# Stromversorgung-3.net
KiCad netlist of a schematic drawn in EAGLE
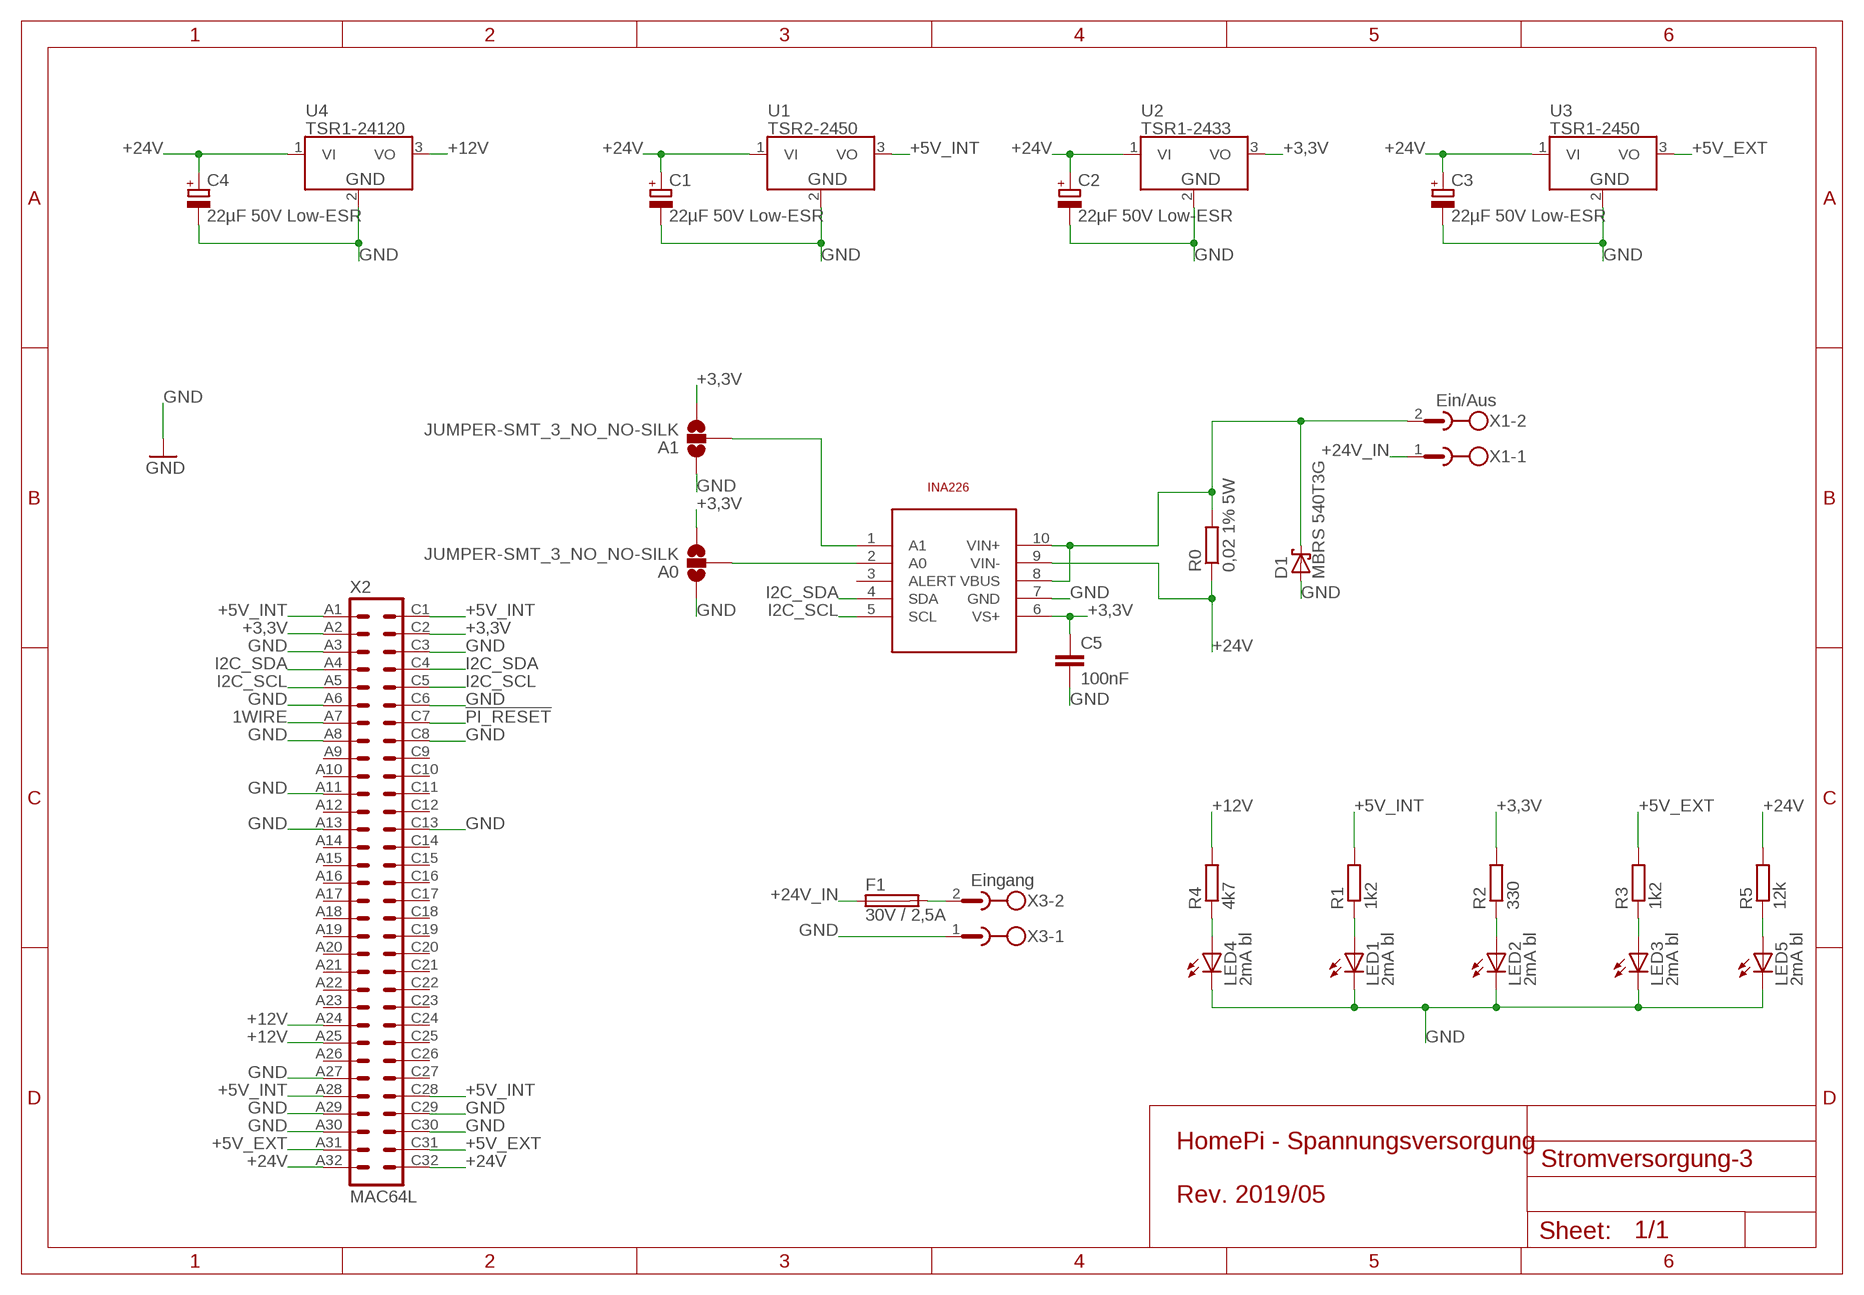
[diagram p0: schematic, sheet 1]

(export (version "E")
  (design (tool "Eeschema 10.0.6"))
  (components
    (comp (ref "A0")
      (value "JUMPER-SMT_3_NO_NO-SILK")
      (footprint "eagle-import:SMT-JUMPER_3_NO_NO-SILK")
      (libsource (lib "eagle-import") (part "JUMPER-SMT_3_NO_NO-SILK"))
    )
    (comp (ref "A1")
      (value "JUMPER-SMT_3_NO_NO-SILK")
      (footprint "eagle-import:SMT-JUMPER_3_NO_NO-SILK")
      (libsource (lib "eagle-import") (part "JUMPER-SMT_3_NO_NO-SILK"))
    )
    (comp (ref "C1")
      (value "22µF 50V Low-ESR")
      (footprint "eagle-import:E2-5")
      (libsource (lib "eagle-import") (part "CPOL-EUE2-5"))
    )
    (comp (ref "C2")
      (value "22µF 50V Low-ESR")
      (footprint "eagle-import:E2-5")
      (libsource (lib "eagle-import") (part "CPOL-EUE2-5"))
    )
    (comp (ref "C3")
      (value "22µF 50V Low-ESR")
      (footprint "eagle-import:E2-5")
      (libsource (lib "eagle-import") (part "CPOL-EUE2-5"))
    )
    (comp (ref "C4")
      (value "22µF 50V Low-ESR")
      (footprint "eagle-import:E2-5")
      (libsource (lib "eagle-import") (part "CPOL-EUE2-5"))
    )
    (comp (ref "C5")
      (value "100nF")
      (footprint "eagle-import:C1206")
      (libsource (lib "eagle-import") (part "C-EUC1206"))
    )
    (comp (ref "D1")
      (value "MBRS 540T3G")
      (footprint "eagle-import:SMC")
      (libsource (lib "eagle-import") (part "SCHOTTKY-DIODESMC"))
    )
    (comp (ref "F1")
      (value "30V / 2,5A")
      (footprint "eagle-import:LITTLEFUSE")
      (libsource (lib "eagle-import") (part "LITTLEFUSE"))
    )
    (comp (ref "IC1")
      (value "TI-INA226")
      (footprint "eagle-import:TI-INA226")
      (libsource (lib "eagle-import") (part "TI-INA226"))
    )
    (comp (ref "LED1")
      (value "2mA bl")
      (footprint "eagle-import:CHIPLED_1206")
      (libsource (lib "eagle-import") (part "LEDCHIPLED_1206"))
    )
    (comp (ref "LED2")
      (value "2mA bl")
      (footprint "eagle-import:CHIPLED_1206")
      (libsource (lib "eagle-import") (part "LEDCHIPLED_1206"))
    )
    (comp (ref "LED3")
      (value "2mA bl")
      (footprint "eagle-import:CHIPLED_1206")
      (libsource (lib "eagle-import") (part "LEDCHIPLED_1206"))
    )
    (comp (ref "LED4")
      (value "2mA bl")
      (footprint "eagle-import:CHIPLED_1206")
      (libsource (lib "eagle-import") (part "LEDCHIPLED_1206"))
    )
    (comp (ref "LED5")
      (value "2mA bl")
      (footprint "eagle-import:CHIPLED_1206")
      (libsource (lib "eagle-import") (part "LEDCHIPLED_1206"))
    )
    (comp (ref "R0")
      (value "0,02 1% 5W")
      (footprint "eagle-import:R2512")
      (libsource (lib "eagle-import") (part "R-EU_R2512"))
    )
    (comp (ref "R1")
      (value "1k2")
      (footprint "eagle-import:R1206")
      (libsource (lib "eagle-import") (part "R-EU_R1206"))
    )
    (comp (ref "R2")
      (value "330")
      (footprint "eagle-import:R1206")
      (libsource (lib "eagle-import") (part "R-EU_R1206"))
    )
    (comp (ref "R3")
      (value "1k2")
      (footprint "eagle-import:R1206")
      (libsource (lib "eagle-import") (part "R-EU_R1206"))
    )
    (comp (ref "R4")
      (value "4k7")
      (footprint "eagle-import:R1206")
      (libsource (lib "eagle-import") (part "R-EU_R1206"))
    )
    (comp (ref "R5")
      (value "12k")
      (footprint "eagle-import:R1206")
      (libsource (lib "eagle-import") (part "R-EU_R1206"))
    )
    (comp (ref "U1")
      (value "TSR2-2450")
      (footprint "eagle-import:TSR2")
      (libsource (lib "eagle-import") (part "TSR2-2450"))
    )
    (comp (ref "U2")
      (value "TSR1-2433")
      (footprint "eagle-import:TSR1")
      (libsource (lib "eagle-import") (part "TSR1-2433"))
    )
    (comp (ref "U3")
      (value "TSR1-2450")
      (footprint "eagle-import:TSR1")
      (libsource (lib "eagle-import") (part "TSR1-2450"))
    )
    (comp (ref "U4")
      (value "TSR1-24120")
      (footprint "eagle-import:TSR1")
      (libsource (lib "eagle-import") (part "TSR1-24120"))
    )
    (comp (ref "X1")
      (value "Ein/Aus")
      (footprint "eagle-import:MSTBA2")
      (fields (field (name "MF") "FARNELL") (field (name "MPN") "1757242"))
      (libsource (lib "eagle-import") (part "MSTBA2"))
    )
    (comp (ref "X2")
      (value "MAC64L")
      (footprint "eagle-import:MAC64L")
      (libsource (lib "eagle-import") (part "MAC64L"))
    )
    (comp (ref "X3")
      (value "Eingang")
      (footprint "eagle-import:MSTBA2")
      (fields (field (name "MF") "FARNELL") (field (name "MPN") "1757242"))
      (libsource (lib "eagle-import") (part "MSTBA2"))
    )
  )
  (nets
    (net (code "1") (name "/+3,3V") (class "Default")
      (node (ref "A0") (pin "3") (pinfunction "3_3") (pintype "passive"))
      (node (ref "A1") (pin "3") (pinfunction "3_3") (pintype "passive"))
      (node (ref "C5") (pin "1") (pinfunction "1_1") (pintype "passive"))
      (node (ref "IC1") (pin "6") (pinfunction "VS+_6") (pintype "bidirectional"))
      (node (ref "R2") (pin "2") (pinfunction "2_2") (pintype "passive"))
      (node (ref "U2") (pin "3") (pinfunction "VO_3") (pintype "power_in"))
      (node (ref "X2") (pin "A2") (pinfunction "A2_A2") (pintype "passive"))
      (node (ref "X2") (pin "C2") (pinfunction "C2_C2") (pintype "passive"))
    )
    (net (code "2") (name "/+5V_EXT") (class "Default")
      (node (ref "R3") (pin "2") (pinfunction "2_2") (pintype "passive"))
      (node (ref "U3") (pin "3") (pinfunction "VO_3") (pintype "power_in"))
      (node (ref "X2") (pin "A31") (pinfunction "A31_A31") (pintype "passive"))
      (node (ref "X2") (pin "C31") (pinfunction "C31_C31") (pintype "passive"))
    )
    (net (code "3") (name "/+5V_INT") (class "Default")
      (node (ref "R1") (pin "2") (pinfunction "2_2") (pintype "passive"))
      (node (ref "U1") (pin "3") (pinfunction "VO_3") (pintype "power_in"))
      (node (ref "X2") (pin "A1") (pinfunction "A1_A1") (pintype "passive"))
      (node (ref "X2") (pin "A28") (pinfunction "A28_A28") (pintype "passive"))
      (node (ref "X2") (pin "C1") (pinfunction "C1_C1") (pintype "passive"))
      (node (ref "X2") (pin "C28") (pinfunction "C28_C28") (pintype "passive"))
    )
    (net (code "4") (name "/+12V") (class "Default")
      (node (ref "R4") (pin "2") (pinfunction "2_2") (pintype "passive"))
      (node (ref "U4") (pin "3") (pinfunction "VO_3") (pintype "power_in"))
      (node (ref "X2") (pin "A24") (pinfunction "A24_A24") (pintype "passive"))
      (node (ref "X2") (pin "A25") (pinfunction "A25_A25") (pintype "passive"))
    )
    (net (code "5") (name "/+24V") (class "Default")
      (node (ref "C1") (pin "+") (pinfunction "+_+") (pintype "passive"))
      (node (ref "C2") (pin "+") (pinfunction "+_+") (pintype "passive"))
      (node (ref "C3") (pin "+") (pinfunction "+_+") (pintype "passive"))
      (node (ref "C4") (pin "+") (pinfunction "+_+") (pintype "passive"))
      (node (ref "IC1") (pin "9") (pinfunction "VIN-_9") (pintype "bidirectional"))
      (node (ref "R0") (pin "1") (pinfunction "1_1") (pintype "passive"))
      (node (ref "R5") (pin "2") (pinfunction "2_2") (pintype "passive"))
      (node (ref "U1") (pin "1") (pinfunction "VI_1") (pintype "power_in"))
      (node (ref "U2") (pin "1") (pinfunction "VI_1") (pintype "power_in"))
      (node (ref "U3") (pin "1") (pinfunction "VI_1") (pintype "power_in"))
      (node (ref "U4") (pin "1") (pinfunction "VI_1") (pintype "power_in"))
      (node (ref "X2") (pin "A32") (pinfunction "A32_A32") (pintype "passive"))
      (node (ref "X2") (pin "C32") (pinfunction "C32_C32") (pintype "passive"))
    )
    (net (code "6") (name "/+24V_IN") (class "Default")
      (node (ref "F1") (pin "1") (pinfunction "1_1") (pintype "passive"))
      (node (ref "X1") (pin "1") (pinfunction "1_1") (pintype "passive"))
    )
    (net (code "7") (name "/1WIRE") (class "Default")
      (node (ref "X2") (pin "A7") (pinfunction "A7_A7") (pintype "passive"))
    )
    (net (code "8") (name "/I2C_SCL") (class "Default")
      (node (ref "IC1") (pin "5") (pinfunction "SCL_5") (pintype "bidirectional"))
      (node (ref "X2") (pin "A5") (pinfunction "A5_A5") (pintype "passive"))
      (node (ref "X2") (pin "C5") (pinfunction "C5_C5") (pintype "passive"))
    )
    (net (code "9") (name "/I2C_SDA") (class "Default")
      (node (ref "IC1") (pin "4") (pinfunction "SDA_4") (pintype "bidirectional"))
      (node (ref "X2") (pin "A4") (pinfunction "A4_A4") (pintype "passive"))
      (node (ref "X2") (pin "C4") (pinfunction "C4_C4") (pintype "passive"))
    )
    (net (code "10") (name "/~{PI_RESET}") (class "Default")
      (node (ref "X2") (pin "C7") (pinfunction "C7_C7") (pintype "passive"))
    )
    (net (code "11") (name "GND") (class "Default")
      (node (ref "A0") (pin "1") (pinfunction "1_1") (pintype "passive"))
      (node (ref "A1") (pin "1") (pinfunction "1_1") (pintype "passive"))
      (node (ref "C1") (pin "-") (pinfunction "-_-") (pintype "passive"))
      (node (ref "C2") (pin "-") (pinfunction "-_-") (pintype "passive"))
      (node (ref "C3") (pin "-") (pinfunction "-_-") (pintype "passive"))
      (node (ref "C4") (pin "-") (pinfunction "-_-") (pintype "passive"))
      (node (ref "C5") (pin "2") (pinfunction "2_2") (pintype "passive"))
      (node (ref "D1") (pin "A") (pinfunction "A_A") (pintype "passive"))
      (node (ref "IC1") (pin "7") (pinfunction "GND_7") (pintype "bidirectional"))
      (node (ref "LED1") (pin "C") (pinfunction "C_C") (pintype "passive"))
      (node (ref "LED2") (pin "C") (pinfunction "C_C") (pintype "passive"))
      (node (ref "LED3") (pin "C") (pinfunction "C_C") (pintype "passive"))
      (node (ref "LED4") (pin "C") (pinfunction "C_C") (pintype "passive"))
      (node (ref "LED5") (pin "C") (pinfunction "C_C") (pintype "passive"))
      (node (ref "U1") (pin "2") (pinfunction "GND_2") (pintype "power_in"))
      (node (ref "U2") (pin "2") (pinfunction "GND_2") (pintype "power_in"))
      (node (ref "U3") (pin "2") (pinfunction "GND_2") (pintype "power_in"))
      (node (ref "U4") (pin "2") (pinfunction "GND_2") (pintype "power_in"))
      (node (ref "X2") (pin "A11") (pinfunction "A11_A11") (pintype "passive"))
      (node (ref "X2") (pin "A13") (pinfunction "A13_A13") (pintype "passive"))
      (node (ref "X2") (pin "A27") (pinfunction "A27_A27") (pintype "passive"))
      (node (ref "X2") (pin "A29") (pinfunction "A29_A29") (pintype "passive"))
      (node (ref "X2") (pin "A3") (pinfunction "A3_A3") (pintype "passive"))
      (node (ref "X2") (pin "A30") (pinfunction "A30_A30") (pintype "passive"))
      (node (ref "X2") (pin "A6") (pinfunction "A6_A6") (pintype "passive"))
      (node (ref "X2") (pin "A8") (pinfunction "A8_A8") (pintype "passive"))
      (node (ref "X2") (pin "C13") (pinfunction "C13_C13") (pintype "passive"))
      (node (ref "X2") (pin "C29") (pinfunction "C29_C29") (pintype "passive"))
      (node (ref "X2") (pin "C3") (pinfunction "C3_C3") (pintype "passive"))
      (node (ref "X2") (pin "C30") (pinfunction "C30_C30") (pintype "passive"))
      (node (ref "X2") (pin "C6") (pinfunction "C6_C6") (pintype "passive"))
      (node (ref "X2") (pin "C8") (pinfunction "C8_C8") (pintype "passive"))
      (node (ref "X3") (pin "1") (pinfunction "1_1") (pintype "passive"))
    )
    (net (code "12") (name "Net-(IC1-A0)") (class "Default")
      (node (ref "A0") (pin "2") (pinfunction "2_2") (pintype "passive"))
      (node (ref "IC1") (pin "2") (pinfunction "A0_2") (pintype "bidirectional"))
    )
    (net (code "13") (name "Net-(IC1-A1)") (class "Default")
      (node (ref "A1") (pin "2") (pinfunction "2_2") (pintype "passive"))
      (node (ref "IC1") (pin "1") (pinfunction "A1_1") (pintype "bidirectional"))
    )
    (net (code "14") (name "Net-(IC1-VBUS)") (class "Default")
      (node (ref "D1") (pin "C") (pinfunction "C_C") (pintype "passive"))
      (node (ref "IC1") (pin "10") (pinfunction "VIN+_10") (pintype "bidirectional"))
      (node (ref "IC1") (pin "8") (pinfunction "VBUS_8") (pintype "bidirectional"))
      (node (ref "R0") (pin "2") (pinfunction "2_2") (pintype "passive"))
      (node (ref "X1") (pin "2") (pinfunction "1_2") (pintype "passive"))
    )
    (net (code "15") (name "Net-(LED1-PadA)") (class "Default")
      (node (ref "LED1") (pin "A") (pinfunction "A_A") (pintype "passive"))
      (node (ref "R1") (pin "1") (pinfunction "1_1") (pintype "passive"))
    )
    (net (code "16") (name "Net-(LED2-PadA)") (class "Default")
      (node (ref "LED2") (pin "A") (pinfunction "A_A") (pintype "passive"))
      (node (ref "R2") (pin "1") (pinfunction "1_1") (pintype "passive"))
    )
    (net (code "17") (name "Net-(LED3-PadA)") (class "Default")
      (node (ref "LED3") (pin "A") (pinfunction "A_A") (pintype "passive"))
      (node (ref "R3") (pin "1") (pinfunction "1_1") (pintype "passive"))
    )
    (net (code "18") (name "Net-(LED4-PadA)") (class "Default")
      (node (ref "LED4") (pin "A") (pinfunction "A_A") (pintype "passive"))
      (node (ref "R4") (pin "1") (pinfunction "1_1") (pintype "passive"))
    )
    (net (code "19") (name "Net-(LED5-PadA)") (class "Default")
      (node (ref "LED5") (pin "A") (pinfunction "A_A") (pintype "passive"))
      (node (ref "R5") (pin "1") (pinfunction "1_1") (pintype "passive"))
    )
    (net (code "20") (name "Net-(X3B-1)") (class "Default")
      (node (ref "F1") (pin "2") (pinfunction "2_2") (pintype "passive"))
      (node (ref "X3") (pin "2") (pinfunction "1_2") (pintype "passive"))
    )
    (net (code "21") (name "unconnected-(IC1-ALERT-Pad3)") (class "Default")
      (node (ref "IC1") (pin "3") (pinfunction "ALERT_3") (pintype "bidirectional"))
    )
    (net (code "22") (name "unconnected-(X2-PadA9)") (class "Default")
      (node (ref "X2") (pin "A9") (pinfunction "A9_A9") (pintype "passive"))
    )
    (net (code "23") (name "unconnected-(X2-PadA10)") (class "Default")
      (node (ref "X2") (pin "A10") (pinfunction "A10_A10") (pintype "passive"))
    )
    (net (code "24") (name "unconnected-(X2-PadA12)") (class "Default")
      (node (ref "X2") (pin "A12") (pinfunction "A12_A12") (pintype "passive"))
    )
    (net (code "25") (name "unconnected-(X2-PadA14)") (class "Default")
      (node (ref "X2") (pin "A14") (pinfunction "A14_A14") (pintype "passive"))
    )
    (net (code "26") (name "unconnected-(X2-PadA15)") (class "Default")
      (node (ref "X2") (pin "A15") (pinfunction "A15_A15") (pintype "passive"))
    )
    (net (code "27") (name "unconnected-(X2-PadA16)") (class "Default")
      (node (ref "X2") (pin "A16") (pinfunction "A16_A16") (pintype "passive"))
    )
    (net (code "28") (name "unconnected-(X2-PadA17)") (class "Default")
      (node (ref "X2") (pin "A17") (pinfunction "A17_A17") (pintype "passive"))
    )
    (net (code "29") (name "unconnected-(X2-PadA18)") (class "Default")
      (node (ref "X2") (pin "A18") (pinfunction "A18_A18") (pintype "passive"))
    )
    (net (code "30") (name "unconnected-(X2-PadA19)") (class "Default")
      (node (ref "X2") (pin "A19") (pinfunction "A19_A19") (pintype "passive"))
    )
    (net (code "31") (name "unconnected-(X2-PadA20)") (class "Default")
      (node (ref "X2") (pin "A20") (pinfunction "A20_A20") (pintype "passive"))
    )
    (net (code "32") (name "unconnected-(X2-PadA21)") (class "Default")
      (node (ref "X2") (pin "A21") (pinfunction "A21_A21") (pintype "passive"))
    )
    (net (code "33") (name "unconnected-(X2-PadA22)") (class "Default")
      (node (ref "X2") (pin "A22") (pinfunction "A22_A22") (pintype "passive"))
    )
    (net (code "34") (name "unconnected-(X2-PadA23)") (class "Default")
      (node (ref "X2") (pin "A23") (pinfunction "A23_A23") (pintype "passive"))
    )
    (net (code "35") (name "unconnected-(X2-PadA26)") (class "Default")
      (node (ref "X2") (pin "A26") (pinfunction "A26_A26") (pintype "passive"))
    )
    (net (code "36") (name "unconnected-(X2-PadC9)") (class "Default")
      (node (ref "X2") (pin "C9") (pinfunction "C9_C9") (pintype "passive"))
    )
    (net (code "37") (name "unconnected-(X2-PadC10)") (class "Default")
      (node (ref "X2") (pin "C10") (pinfunction "C10_C10") (pintype "passive"))
    )
    (net (code "38") (name "unconnected-(X2-PadC11)") (class "Default")
      (node (ref "X2") (pin "C11") (pinfunction "C11_C11") (pintype "passive"))
    )
    (net (code "39") (name "unconnected-(X2-PadC12)") (class "Default")
      (node (ref "X2") (pin "C12") (pinfunction "C12_C12") (pintype "passive"))
    )
    (net (code "40") (name "unconnected-(X2-PadC14)") (class "Default")
      (node (ref "X2") (pin "C14") (pinfunction "C14_C14") (pintype "passive"))
    )
    (net (code "41") (name "unconnected-(X2-PadC15)") (class "Default")
      (node (ref "X2") (pin "C15") (pinfunction "C15_C15") (pintype "passive"))
    )
    (net (code "42") (name "unconnected-(X2-PadC16)") (class "Default")
      (node (ref "X2") (pin "C16") (pinfunction "C16_C16") (pintype "passive"))
    )
    (net (code "43") (name "unconnected-(X2-PadC17)") (class "Default")
      (node (ref "X2") (pin "C17") (pinfunction "C17_C17") (pintype "passive"))
    )
    (net (code "44") (name "unconnected-(X2-PadC18)") (class "Default")
      (node (ref "X2") (pin "C18") (pinfunction "C18_C18") (pintype "passive"))
    )
    (net (code "45") (name "unconnected-(X2-PadC19)") (class "Default")
      (node (ref "X2") (pin "C19") (pinfunction "C19_C19") (pintype "passive"))
    )
    (net (code "46") (name "unconnected-(X2-PadC20)") (class "Default")
      (node (ref "X2") (pin "C20") (pinfunction "C20_C20") (pintype "passive"))
    )
    (net (code "47") (name "unconnected-(X2-PadC21)") (class "Default")
      (node (ref "X2") (pin "C21") (pinfunction "C21_C21") (pintype "passive"))
    )
    (net (code "48") (name "unconnected-(X2-PadC22)") (class "Default")
      (node (ref "X2") (pin "C22") (pinfunction "C22_C22") (pintype "passive"))
    )
    (net (code "49") (name "unconnected-(X2-PadC23)") (class "Default")
      (node (ref "X2") (pin "C23") (pinfunction "C23_C23") (pintype "passive"))
    )
    (net (code "50") (name "unconnected-(X2-PadC24)") (class "Default")
      (node (ref "X2") (pin "C24") (pinfunction "C24_C24") (pintype "passive"))
    )
    (net (code "51") (name "unconnected-(X2-PadC25)") (class "Default")
      (node (ref "X2") (pin "C25") (pinfunction "C25_C25") (pintype "passive"))
    )
    (net (code "52") (name "unconnected-(X2-PadC26)") (class "Default")
      (node (ref "X2") (pin "C26") (pinfunction "C26_C26") (pintype "passive"))
    )
    (net (code "53") (name "unconnected-(X2-PadC27)") (class "Default")
      (node (ref "X2") (pin "C27") (pinfunction "C27_C27") (pintype "passive"))
    )
  )
)
